# Load.net
KiCad netlist of a schematic drawn in Altium Designer
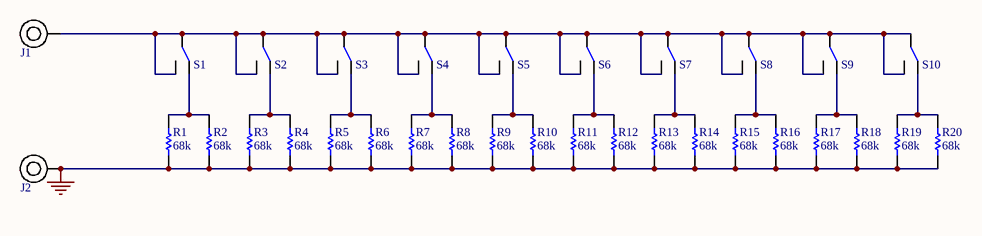
[diagram p0: Load.SchDoc]

(export (version "E")
  (design (tool "Eeschema 10.0.6"))
  (components
    (comp (ref "J1")
      (value "575-8")
      (footprint "575-8")
      (description "Keystone PCB banana jack")
      (libsource (lib "Connectors") (part "575-8"))
    )
    (comp (ref "J2")
      (value "575-8")
      (footprint "575-8")
      (description "Keystone PCB banana jack")
      (libsource (lib "Connectors") (part "575-8"))
    )
    (comp (ref "R1")
      (value "68k")
      (footprint "KOA MOS1")
      (description "Metal Oxide Resistors 68K ohm 5% 1W")
      (fields
        (field (name "MANUFACTURER") "KOA Speer")
        (field (name "MANUFACTURER PART NUMBER") "MOS1CT52R183J")
      )
      (libsource (lib "Misc resistors") (part "MOS1CT528R683J"))
    )
    (comp (ref "R2")
      (value "68k")
      (footprint "KOA MOS1")
      (description "Metal Oxide Resistors 68K ohm 5% 1W")
      (fields
        (field (name "MANUFACTURER") "KOA Speer")
        (field (name "MANUFACTURER PART NUMBER") "MOS1CT52R183J")
      )
      (libsource (lib "Misc resistors") (part "MOS1CT528R683J"))
    )
    (comp (ref "R3")
      (value "68k")
      (footprint "KOA MOS1")
      (description "Metal Oxide Resistors 68K ohm 5% 1W")
      (fields
        (field (name "MANUFACTURER") "KOA Speer")
        (field (name "MANUFACTURER PART NUMBER") "MOS1CT52R183J")
      )
      (libsource (lib "Misc resistors") (part "MOS1CT528R683J"))
    )
    (comp (ref "R4")
      (value "68k")
      (footprint "KOA MOS1")
      (description "Metal Oxide Resistors 68K ohm 5% 1W")
      (fields
        (field (name "MANUFACTURER") "KOA Speer")
        (field (name "MANUFACTURER PART NUMBER") "MOS1CT52R183J")
      )
      (libsource (lib "Misc resistors") (part "MOS1CT528R683J"))
    )
    (comp (ref "R5")
      (value "68k")
      (footprint "KOA MOS1")
      (description "Metal Oxide Resistors 68K ohm 5% 1W")
      (fields
        (field (name "MANUFACTURER") "KOA Speer")
        (field (name "MANUFACTURER PART NUMBER") "MOS1CT52R183J")
      )
      (libsource (lib "Misc resistors") (part "MOS1CT528R683J"))
    )
    (comp (ref "R6")
      (value "68k")
      (footprint "KOA MOS1")
      (description "Metal Oxide Resistors 68K ohm 5% 1W")
      (fields
        (field (name "MANUFACTURER") "KOA Speer")
        (field (name "MANUFACTURER PART NUMBER") "MOS1CT52R183J")
      )
      (libsource (lib "Misc resistors") (part "MOS1CT528R683J"))
    )
    (comp (ref "R7")
      (value "68k")
      (footprint "KOA MOS1")
      (description "Metal Oxide Resistors 68K ohm 5% 1W")
      (fields
        (field (name "MANUFACTURER") "KOA Speer")
        (field (name "MANUFACTURER PART NUMBER") "MOS1CT52R183J")
      )
      (libsource (lib "Misc resistors") (part "MOS1CT528R683J"))
    )
    (comp (ref "R8")
      (value "68k")
      (footprint "KOA MOS1")
      (description "Metal Oxide Resistors 68K ohm 5% 1W")
      (fields
        (field (name "MANUFACTURER") "KOA Speer")
        (field (name "MANUFACTURER PART NUMBER") "MOS1CT52R183J")
      )
      (libsource (lib "Misc resistors") (part "MOS1CT528R683J"))
    )
    (comp (ref "R9")
      (value "68k")
      (footprint "KOA MOS1")
      (description "Metal Oxide Resistors 68K ohm 5% 1W")
      (fields
        (field (name "MANUFACTURER") "KOA Speer")
        (field (name "MANUFACTURER PART NUMBER") "MOS1CT52R183J")
      )
      (libsource (lib "Misc resistors") (part "MOS1CT528R683J"))
    )
    (comp (ref "R10")
      (value "68k")
      (footprint "KOA MOS1")
      (description "Metal Oxide Resistors 68K ohm 5% 1W")
      (fields
        (field (name "MANUFACTURER") "KOA Speer")
        (field (name "MANUFACTURER PART NUMBER") "MOS1CT52R183J")
      )
      (libsource (lib "Misc resistors") (part "MOS1CT528R683J"))
    )
    (comp (ref "R11")
      (value "68k")
      (footprint "KOA MOS1")
      (description "Metal Oxide Resistors 68K ohm 5% 1W")
      (fields
        (field (name "MANUFACTURER") "KOA Speer")
        (field (name "MANUFACTURER PART NUMBER") "MOS1CT52R183J")
      )
      (libsource (lib "Misc resistors") (part "MOS1CT528R683J"))
    )
    (comp (ref "R12")
      (value "68k")
      (footprint "KOA MOS1")
      (description "Metal Oxide Resistors 68K ohm 5% 1W")
      (fields
        (field (name "MANUFACTURER") "KOA Speer")
        (field (name "MANUFACTURER PART NUMBER") "MOS1CT52R183J")
      )
      (libsource (lib "Misc resistors") (part "MOS1CT528R683J"))
    )
    (comp (ref "R13")
      (value "68k")
      (footprint "KOA MOS1")
      (description "Metal Oxide Resistors 68K ohm 5% 1W")
      (fields
        (field (name "MANUFACTURER") "KOA Speer")
        (field (name "MANUFACTURER PART NUMBER") "MOS1CT52R183J")
      )
      (libsource (lib "Misc resistors") (part "MOS1CT528R683J"))
    )
    (comp (ref "R14")
      (value "68k")
      (footprint "KOA MOS1")
      (description "Metal Oxide Resistors 68K ohm 5% 1W")
      (fields
        (field (name "MANUFACTURER") "KOA Speer")
        (field (name "MANUFACTURER PART NUMBER") "MOS1CT52R183J")
      )
      (libsource (lib "Misc resistors") (part "MOS1CT528R683J"))
    )
    (comp (ref "R15")
      (value "68k")
      (footprint "KOA MOS1")
      (description "Metal Oxide Resistors 68K ohm 5% 1W")
      (fields
        (field (name "MANUFACTURER") "KOA Speer")
        (field (name "MANUFACTURER PART NUMBER") "MOS1CT52R183J")
      )
      (libsource (lib "Misc resistors") (part "MOS1CT528R683J"))
    )
    (comp (ref "R16")
      (value "68k")
      (footprint "KOA MOS1")
      (description "Metal Oxide Resistors 68K ohm 5% 1W")
      (fields
        (field (name "MANUFACTURER") "KOA Speer")
        (field (name "MANUFACTURER PART NUMBER") "MOS1CT52R183J")
      )
      (libsource (lib "Misc resistors") (part "MOS1CT528R683J"))
    )
    (comp (ref "R17")
      (value "68k")
      (footprint "KOA MOS1")
      (description "Metal Oxide Resistors 68K ohm 5% 1W")
      (fields
        (field (name "MANUFACTURER") "KOA Speer")
        (field (name "MANUFACTURER PART NUMBER") "MOS1CT52R183J")
      )
      (libsource (lib "Misc resistors") (part "MOS1CT528R683J"))
    )
    (comp (ref "R18")
      (value "68k")
      (footprint "KOA MOS1")
      (description "Metal Oxide Resistors 68K ohm 5% 1W")
      (fields
        (field (name "MANUFACTURER") "KOA Speer")
        (field (name "MANUFACTURER PART NUMBER") "MOS1CT52R183J")
      )
      (libsource (lib "Misc resistors") (part "MOS1CT528R683J"))
    )
    (comp (ref "R19")
      (value "68k")
      (footprint "KOA MOS1")
      (description "Metal Oxide Resistors 68K ohm 5% 1W")
      (fields
        (field (name "MANUFACTURER") "KOA Speer")
        (field (name "MANUFACTURER PART NUMBER") "MOS1CT52R183J")
      )
      (libsource (lib "Misc resistors") (part "MOS1CT528R683J"))
    )
    (comp (ref "R20")
      (value "68k")
      (footprint "KOA MOS1")
      (description "Metal Oxide Resistors 68K ohm 5% 1W")
      (fields
        (field (name "MANUFACTURER") "KOA Speer")
        (field (name "MANUFACTURER PART NUMBER") "MOS1CT52R183J")
      )
      (libsource (lib "Misc resistors") (part "MOS1CT528R683J"))
    )
    (comp (ref "S1")
      (value "OS102011MS2QN1")
      (footprint "OS102011MS2QN1")
      (description "SPDT slide switch")
      (fields (field (name "MANUFACTURER") "ITT C&K"))
      (libsource (lib "Connectors") (part "OS102011MS2QN1"))
    )
    (comp (ref "S2")
      (value "OS102011MS2QN1")
      (footprint "OS102011MS2QN1")
      (description "SPDT slide switch")
      (fields (field (name "MANUFACTURER") "ITT C&K"))
      (libsource (lib "Connectors") (part "OS102011MS2QN1"))
    )
    (comp (ref "S3")
      (value "OS102011MS2QN1")
      (footprint "OS102011MS2QN1")
      (description "SPDT slide switch")
      (fields (field (name "MANUFACTURER") "ITT C&K"))
      (libsource (lib "Connectors") (part "OS102011MS2QN1"))
    )
    (comp (ref "S4")
      (value "OS102011MS2QN1")
      (footprint "OS102011MS2QN1")
      (description "SPDT slide switch")
      (fields (field (name "MANUFACTURER") "ITT C&K"))
      (libsource (lib "Connectors") (part "OS102011MS2QN1"))
    )
    (comp (ref "S5")
      (value "OS102011MS2QN1")
      (footprint "OS102011MS2QN1")
      (description "SPDT slide switch")
      (fields (field (name "MANUFACTURER") "ITT C&K"))
      (libsource (lib "Connectors") (part "OS102011MS2QN1"))
    )
    (comp (ref "S6")
      (value "OS102011MS2QN1")
      (footprint "OS102011MS2QN1")
      (description "SPDT slide switch")
      (fields (field (name "MANUFACTURER") "ITT C&K"))
      (libsource (lib "Connectors") (part "OS102011MS2QN1"))
    )
    (comp (ref "S7")
      (value "OS102011MS2QN1")
      (footprint "OS102011MS2QN1")
      (description "SPDT slide switch")
      (fields (field (name "MANUFACTURER") "ITT C&K"))
      (libsource (lib "Connectors") (part "OS102011MS2QN1"))
    )
    (comp (ref "S8")
      (value "OS102011MS2QN1")
      (footprint "OS102011MS2QN1")
      (description "SPDT slide switch")
      (fields (field (name "MANUFACTURER") "ITT C&K"))
      (libsource (lib "Connectors") (part "OS102011MS2QN1"))
    )
    (comp (ref "S9")
      (value "OS102011MS2QN1")
      (footprint "OS102011MS2QN1")
      (description "SPDT slide switch")
      (fields (field (name "MANUFACTURER") "ITT C&K"))
      (libsource (lib "Connectors") (part "OS102011MS2QN1"))
    )
    (comp (ref "S10")
      (value "OS102011MS2QN1")
      (footprint "OS102011MS2QN1")
      (description "SPDT slide switch")
      (fields (field (name "MANUFACTURER") "ITT C&K"))
      (libsource (lib "Connectors") (part "OS102011MS2QN1"))
    )
  )
  (nets
    (net (code "1") (name "GND") (class "Default")
      (node (ref "J2") (pin "1") (pinfunction "1_1") (pintype "passive"))
      (node (ref "R1") (pin "1") (pinfunction "1_1") (pintype "passive"))
      (node (ref "R10") (pin "1") (pinfunction "1_1") (pintype "passive"))
      (node (ref "R11") (pin "1") (pinfunction "1_1") (pintype "passive"))
      (node (ref "R12") (pin "1") (pinfunction "1_1") (pintype "passive"))
      (node (ref "R13") (pin "1") (pinfunction "1_1") (pintype "passive"))
      (node (ref "R14") (pin "1") (pinfunction "1_1") (pintype "passive"))
      (node (ref "R15") (pin "1") (pinfunction "1_1") (pintype "passive"))
      (node (ref "R16") (pin "1") (pinfunction "1_1") (pintype "passive"))
      (node (ref "R17") (pin "1") (pinfunction "1_1") (pintype "passive"))
      (node (ref "R18") (pin "1") (pinfunction "1_1") (pintype "passive"))
      (node (ref "R19") (pin "1") (pinfunction "1_1") (pintype "passive"))
      (node (ref "R2") (pin "1") (pinfunction "1_1") (pintype "passive"))
      (node (ref "R20") (pin "1") (pinfunction "1_1") (pintype "passive"))
      (node (ref "R3") (pin "1") (pinfunction "1_1") (pintype "passive"))
      (node (ref "R4") (pin "1") (pinfunction "1_1") (pintype "passive"))
      (node (ref "R5") (pin "1") (pinfunction "1_1") (pintype "passive"))
      (node (ref "R6") (pin "1") (pinfunction "1_1") (pintype "passive"))
      (node (ref "R7") (pin "1") (pinfunction "1_1") (pintype "passive"))
      (node (ref "R8") (pin "1") (pinfunction "1_1") (pintype "passive"))
      (node (ref "R9") (pin "1") (pinfunction "1_1") (pintype "passive"))
    )
    (net (code "2") (name "Net-(J1-Pad1)") (class "Default")
      (node (ref "J1") (pin "1") (pinfunction "1_1") (pintype "passive"))
      (node (ref "S1") (pin "2") (pinfunction "2_2") (pintype "passive"))
      (node (ref "S1") (pin "3") (pinfunction "3_3") (pintype "passive"))
      (node (ref "S10") (pin "2") (pinfunction "2_2") (pintype "passive"))
      (node (ref "S10") (pin "3") (pinfunction "3_3") (pintype "passive"))
      (node (ref "S2") (pin "2") (pinfunction "2_2") (pintype "passive"))
      (node (ref "S2") (pin "3") (pinfunction "3_3") (pintype "passive"))
      (node (ref "S3") (pin "2") (pinfunction "2_2") (pintype "passive"))
      (node (ref "S3") (pin "3") (pinfunction "3_3") (pintype "passive"))
      (node (ref "S4") (pin "2") (pinfunction "2_2") (pintype "passive"))
      (node (ref "S4") (pin "3") (pinfunction "3_3") (pintype "passive"))
      (node (ref "S5") (pin "2") (pinfunction "2_2") (pintype "passive"))
      (node (ref "S5") (pin "3") (pinfunction "3_3") (pintype "passive"))
      (node (ref "S6") (pin "2") (pinfunction "2_2") (pintype "passive"))
      (node (ref "S6") (pin "3") (pinfunction "3_3") (pintype "passive"))
      (node (ref "S7") (pin "2") (pinfunction "2_2") (pintype "passive"))
      (node (ref "S7") (pin "3") (pinfunction "3_3") (pintype "passive"))
      (node (ref "S8") (pin "2") (pinfunction "2_2") (pintype "passive"))
      (node (ref "S8") (pin "3") (pinfunction "3_3") (pintype "passive"))
      (node (ref "S9") (pin "2") (pinfunction "2_2") (pintype "passive"))
      (node (ref "S9") (pin "3") (pinfunction "3_3") (pintype "passive"))
    )
    (net (code "3") (name "Net-(R1-Pad2)") (class "Default")
      (node (ref "R1") (pin "2") (pinfunction "2_2") (pintype "passive"))
      (node (ref "R2") (pin "2") (pinfunction "2_2") (pintype "passive"))
      (node (ref "S1") (pin "1") (pinfunction "1_1") (pintype "passive"))
    )
    (net (code "4") (name "Net-(R3-Pad2)") (class "Default")
      (node (ref "R3") (pin "2") (pinfunction "2_2") (pintype "passive"))
      (node (ref "R4") (pin "2") (pinfunction "2_2") (pintype "passive"))
      (node (ref "S2") (pin "1") (pinfunction "1_1") (pintype "passive"))
    )
    (net (code "5") (name "Net-(R5-Pad2)") (class "Default")
      (node (ref "R5") (pin "2") (pinfunction "2_2") (pintype "passive"))
      (node (ref "R6") (pin "2") (pinfunction "2_2") (pintype "passive"))
      (node (ref "S3") (pin "1") (pinfunction "1_1") (pintype "passive"))
    )
    (net (code "6") (name "Net-(R7-Pad2)") (class "Default")
      (node (ref "R7") (pin "2") (pinfunction "2_2") (pintype "passive"))
      (node (ref "R8") (pin "2") (pinfunction "2_2") (pintype "passive"))
      (node (ref "S4") (pin "1") (pinfunction "1_1") (pintype "passive"))
    )
    (net (code "7") (name "Net-(R10-Pad2)") (class "Default")
      (node (ref "R10") (pin "2") (pinfunction "2_2") (pintype "passive"))
      (node (ref "R9") (pin "2") (pinfunction "2_2") (pintype "passive"))
      (node (ref "S5") (pin "1") (pinfunction "1_1") (pintype "passive"))
    )
    (net (code "8") (name "Net-(R11-Pad2)") (class "Default")
      (node (ref "R11") (pin "2") (pinfunction "2_2") (pintype "passive"))
      (node (ref "R12") (pin "2") (pinfunction "2_2") (pintype "passive"))
      (node (ref "S6") (pin "1") (pinfunction "1_1") (pintype "passive"))
    )
    (net (code "9") (name "Net-(R13-Pad2)") (class "Default")
      (node (ref "R13") (pin "2") (pinfunction "2_2") (pintype "passive"))
      (node (ref "R14") (pin "2") (pinfunction "2_2") (pintype "passive"))
      (node (ref "S7") (pin "1") (pinfunction "1_1") (pintype "passive"))
    )
    (net (code "10") (name "Net-(R15-Pad2)") (class "Default")
      (node (ref "R15") (pin "2") (pinfunction "2_2") (pintype "passive"))
      (node (ref "R16") (pin "2") (pinfunction "2_2") (pintype "passive"))
      (node (ref "S8") (pin "1") (pinfunction "1_1") (pintype "passive"))
    )
    (net (code "11") (name "Net-(R17-Pad2)") (class "Default")
      (node (ref "R17") (pin "2") (pinfunction "2_2") (pintype "passive"))
      (node (ref "R18") (pin "2") (pinfunction "2_2") (pintype "passive"))
      (node (ref "S9") (pin "1") (pinfunction "1_1") (pintype "passive"))
    )
    (net (code "12") (name "Net-(R19-Pad2)") (class "Default")
      (node (ref "R19") (pin "2") (pinfunction "2_2") (pintype "passive"))
      (node (ref "R20") (pin "2") (pinfunction "2_2") (pintype "passive"))
      (node (ref "S10") (pin "1") (pinfunction "1_1") (pintype "passive"))
    )
  )
)
